# CCM_0021.net
KiCad netlist of a schematic drawn in EAGLE
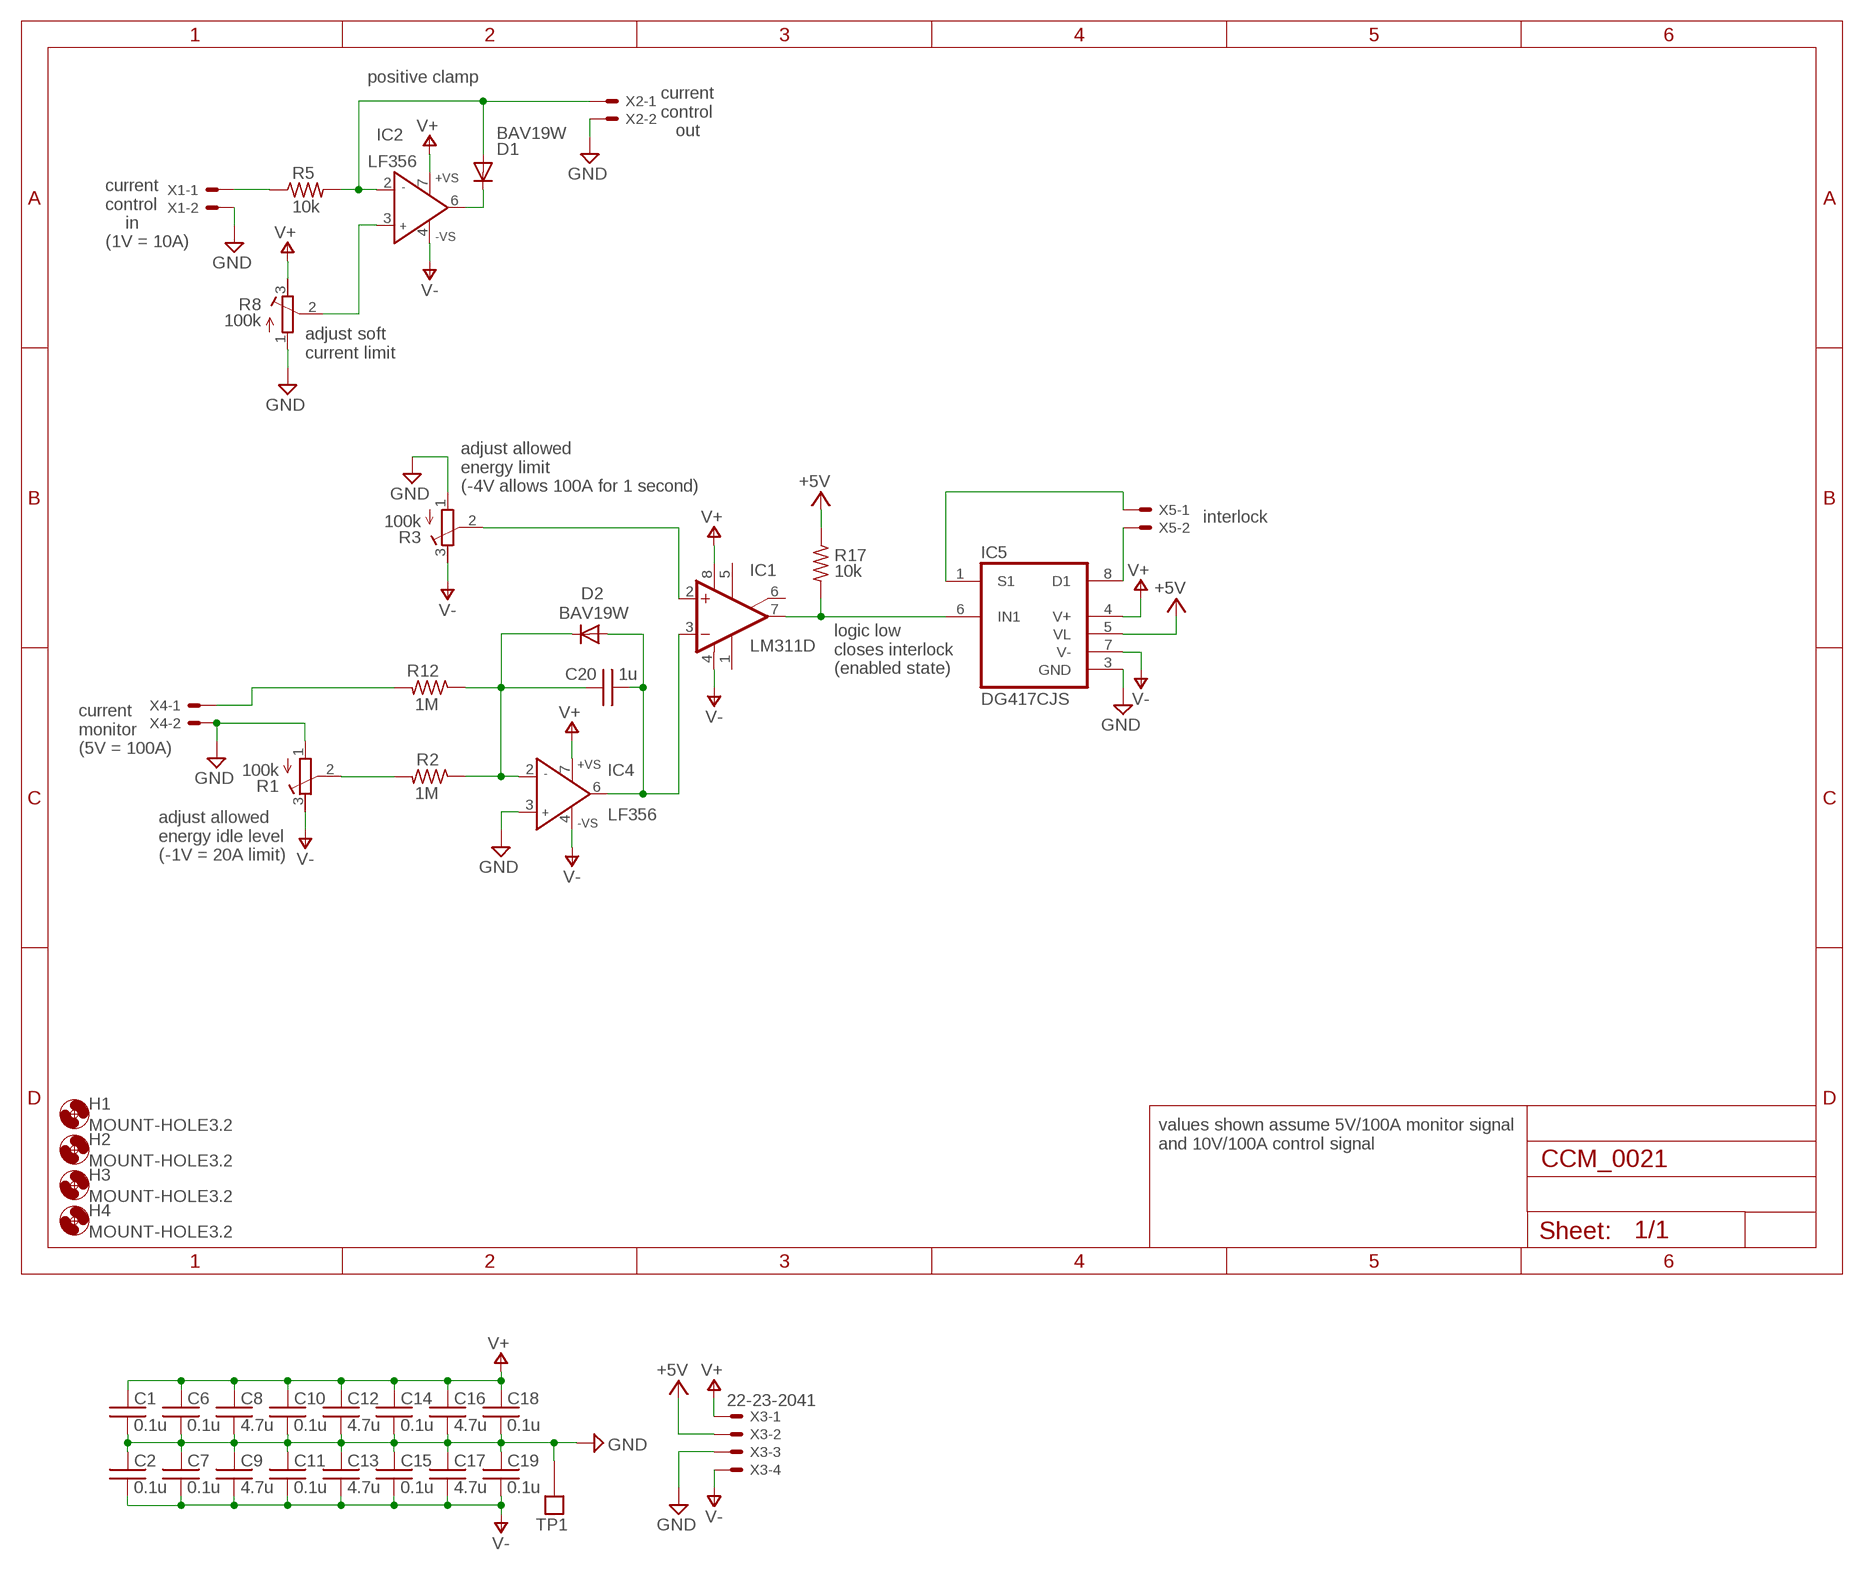
[diagram p0: schematic, sheet 1]

(export (version "E")
  (design (tool "Eeschema 10.0.6"))
  (components
    (comp (ref "C1")
      (value "0.1u")
      (footprint "eagle-import:0603")
      (libsource (lib "eagle-import") (part "C0603"))
    )
    (comp (ref "C2")
      (value "0.1u")
      (footprint "eagle-import:0603")
      (libsource (lib "eagle-import") (part "C0603"))
    )
    (comp (ref "C6")
      (value "0.1u")
      (footprint "eagle-import:0603")
      (libsource (lib "eagle-import") (part "C0603"))
    )
    (comp (ref "C7")
      (value "0.1u")
      (footprint "eagle-import:0603")
      (libsource (lib "eagle-import") (part "C0603"))
    )
    (comp (ref "C8")
      (value "4.7u")
      (footprint "eagle-import:0603")
      (libsource (lib "eagle-import") (part "C0603"))
    )
    (comp (ref "C9")
      (value "4.7u")
      (footprint "eagle-import:0603")
      (libsource (lib "eagle-import") (part "C0603"))
    )
    (comp (ref "C10")
      (value "0.1u")
      (footprint "eagle-import:0603")
      (libsource (lib "eagle-import") (part "C0603"))
    )
    (comp (ref "C11")
      (value "0.1u")
      (footprint "eagle-import:0603")
      (libsource (lib "eagle-import") (part "C0603"))
    )
    (comp (ref "C12")
      (value "4.7u")
      (footprint "eagle-import:0603")
      (libsource (lib "eagle-import") (part "C0603"))
    )
    (comp (ref "C13")
      (value "4.7u")
      (footprint "eagle-import:0603")
      (libsource (lib "eagle-import") (part "C0603"))
    )
    (comp (ref "C14")
      (value "0.1u")
      (footprint "eagle-import:0603")
      (libsource (lib "eagle-import") (part "C0603"))
    )
    (comp (ref "C15")
      (value "0.1u")
      (footprint "eagle-import:0603")
      (libsource (lib "eagle-import") (part "C0603"))
    )
    (comp (ref "C16")
      (value "4.7u")
      (footprint "eagle-import:0603")
      (libsource (lib "eagle-import") (part "C0603"))
    )
    (comp (ref "C17")
      (value "4.7u")
      (footprint "eagle-import:0603")
      (libsource (lib "eagle-import") (part "C0603"))
    )
    (comp (ref "C18")
      (value "0.1u")
      (footprint "eagle-import:0603")
      (libsource (lib "eagle-import") (part "C0603"))
    )
    (comp (ref "C19")
      (value "0.1u")
      (footprint "eagle-import:0603")
      (libsource (lib "eagle-import") (part "C0603"))
    )
    (comp (ref "C20")
      (value "1u")
      (footprint "eagle-import:0603")
      (libsource (lib "eagle-import") (part "C0603"))
    )
    (comp (ref "D1")
      (value "BAV19W")
      (footprint "eagle-import:SOD123")
      (libsource (lib "eagle-import") (part "DIODE-SOD123"))
    )
    (comp (ref "D2")
      (value "BAV19W")
      (footprint "eagle-import:SOD123")
      (libsource (lib "eagle-import") (part "DIODE-SOD123"))
    )
    (comp (ref "H1")
      (value "MOUNT-HOLE3.2")
      (footprint "eagle-import:3,2")
      (libsource (lib "eagle-import") (part "MOUNT-HOLE3.2"))
    )
    (comp (ref "H2")
      (value "MOUNT-HOLE3.2")
      (footprint "eagle-import:3,2")
      (libsource (lib "eagle-import") (part "MOUNT-HOLE3.2"))
    )
    (comp (ref "H3")
      (value "MOUNT-HOLE3.2")
      (footprint "eagle-import:3,2")
      (libsource (lib "eagle-import") (part "MOUNT-HOLE3.2"))
    )
    (comp (ref "H4")
      (value "MOUNT-HOLE3.2")
      (footprint "eagle-import:3,2")
      (libsource (lib "eagle-import") (part "MOUNT-HOLE3.2"))
    )
    (comp (ref "IC1")
      (value "LM311D")
      (footprint "eagle-import:SO08")
      (libsource (lib "eagle-import") (part "LM311D"))
    )
    (comp (ref "IC2")
      (value "LF356")
      (footprint "eagle-import:SO8")
      (fields (field (name "MF") "ALTERA CORPORATION") (field (name "MPN") "AD825ARZ"))
      (libsource (lib "eagle-import") (part "AD825_BR"))
    )
    (comp (ref "IC4")
      (value "LF356")
      (footprint "eagle-import:SO8")
      (fields (field (name "MF") "ALTERA CORPORATION") (field (name "MPN") "AD825ARZ"))
      (libsource (lib "eagle-import") (part "AD825_BR"))
    )
    (comp (ref "IC5")
      (value "DG417CJS")
      (footprint "eagle-import:SO8")
      (libsource (lib "eagle-import") (part "DG417CJS"))
    )
    (comp (ref "R1")
      (value "100k")
      (footprint "eagle-import:RTRIM3296W")
      (libsource (lib "eagle-import") (part "R-TRIMM3296W"))
    )
    (comp (ref "R2")
      (value "1M")
      (footprint "eagle-import:0603")
      (libsource (lib "eagle-import") (part "R0603"))
    )
    (comp (ref "R3")
      (value "100k")
      (footprint "eagle-import:RTRIM3296W")
      (libsource (lib "eagle-import") (part "R-TRIMM3296W"))
    )
    (comp (ref "R5")
      (value "10k")
      (footprint "eagle-import:0603")
      (libsource (lib "eagle-import") (part "R0603"))
    )
    (comp (ref "R8")
      (value "100k")
      (footprint "eagle-import:RTRIM3296W")
      (libsource (lib "eagle-import") (part "R-TRIMM3296W"))
    )
    (comp (ref "R12")
      (value "1M")
      (footprint "eagle-import:0603")
      (libsource (lib "eagle-import") (part "R0603"))
    )
    (comp (ref "R17")
      (value "10k")
      (footprint "eagle-import:0603")
      (libsource (lib "eagle-import") (part "R0603"))
    )
    (comp (ref "TP1")
      (value "TESTPOINT")
      (footprint "eagle-import:TESTPOINT")
      (libsource (lib "eagle-import") (part "TESTPOINT"))
    )
    (comp (ref "X1")
      (value "22-23-2021")
      (footprint "eagle-import:22-23-2021")
      (fields (field (name "MF") "MOLEX") (field (name "SPICEPREFIX") "X"))
      (libsource (lib "eagle-import") (part "22-23-2021"))
    )
    (comp (ref "X2")
      (value "22-23-2021")
      (footprint "eagle-import:22-23-2021")
      (fields (field (name "MF") "MOLEX"))
      (libsource (lib "eagle-import") (part "22-23-2021"))
    )
    (comp (ref "X3")
      (value "22-23-2041")
      (footprint "eagle-import:22-23-2041")
      (fields (field (name "MF") "MOLEX"))
      (libsource (lib "eagle-import") (part "22-23-2041"))
    )
    (comp (ref "X4")
      (value "22-23-2021")
      (footprint "eagle-import:22-23-2021")
      (fields (field (name "MF") "MOLEX") (field (name "SPICEPREFIX") "X"))
      (libsource (lib "eagle-import") (part "22-23-2021"))
    )
    (comp (ref "X5")
      (value "22-23-2021")
      (footprint "eagle-import:22-23-2021")
      (fields (field (name "MF") "MOLEX"))
      (libsource (lib "eagle-import") (part "22-23-2021"))
    )
  )
  (nets
    (net (code "1") (name "+5V") (class "Default")
      (node (ref "IC5") (pin "5") (pinfunction "VL_5") (pintype "power_in"))
      (node (ref "R17") (pin "1") (pinfunction "1_1") (pintype "passive"))
      (node (ref "X3") (pin "2") (pinfunction "S_2") (pintype "passive"))
    )
    (net (code "2") (name "GND") (class "Default")
      (node (ref "C1") (pin "2") (pinfunction "2_2") (pintype "passive"))
      (node (ref "C10") (pin "2") (pinfunction "2_2") (pintype "passive"))
      (node (ref "C11") (pin "1") (pinfunction "1_1") (pintype "passive"))
      (node (ref "C12") (pin "2") (pinfunction "2_2") (pintype "passive"))
      (node (ref "C13") (pin "1") (pinfunction "1_1") (pintype "passive"))
      (node (ref "C14") (pin "2") (pinfunction "2_2") (pintype "passive"))
      (node (ref "C15") (pin "1") (pinfunction "1_1") (pintype "passive"))
      (node (ref "C16") (pin "2") (pinfunction "2_2") (pintype "passive"))
      (node (ref "C17") (pin "1") (pinfunction "1_1") (pintype "passive"))
      (node (ref "C18") (pin "2") (pinfunction "2_2") (pintype "passive"))
      (node (ref "C19") (pin "1") (pinfunction "1_1") (pintype "passive"))
      (node (ref "C2") (pin "1") (pinfunction "1_1") (pintype "passive"))
      (node (ref "C6") (pin "2") (pinfunction "2_2") (pintype "passive"))
      (node (ref "C7") (pin "1") (pinfunction "1_1") (pintype "passive"))
      (node (ref "C8") (pin "2") (pinfunction "2_2") (pintype "passive"))
      (node (ref "C9") (pin "1") (pinfunction "1_1") (pintype "passive"))
      (node (ref "IC4") (pin "3") (pinfunction "IN+_3") (pintype "input"))
      (node (ref "IC5") (pin "3") (pinfunction "GND_3") (pintype "power_in"))
      (node (ref "R1") (pin "1") (pinfunction "A_1") (pintype "passive"))
      (node (ref "R3") (pin "1") (pinfunction "A_1") (pintype "passive"))
      (node (ref "R8") (pin "1") (pinfunction "A_1") (pintype "passive"))
      (node (ref "TP1") (pin "P$1") (pinfunction "P$1_P$1") (pintype "bidirectional"))
      (node (ref "X1") (pin "2") (pinfunction "S_2") (pintype "passive"))
      (node (ref "X2") (pin "2") (pinfunction "S_2") (pintype "passive"))
      (node (ref "X3") (pin "3") (pinfunction "S_3") (pintype "passive"))
      (node (ref "X4") (pin "2") (pinfunction "S_2") (pintype "passive"))
    )
    (net (code "3") (name "Net-(IC1-+IN)") (class "Default")
      (node (ref "IC1") (pin "2") (pinfunction "+IN_2") (pintype "input"))
      (node (ref "R3") (pin "2") (pinfunction "S_2") (pintype "passive"))
    )
    (net (code "4") (name "Net-(IC1--IN)") (class "Default")
      (node (ref "C20") (pin "1") (pinfunction "1_1") (pintype "passive"))
      (node (ref "D2") (pin "A") (pinfunction "A_A") (pintype "passive"))
      (node (ref "IC1") (pin "3") (pinfunction "-IN_3") (pintype "input"))
      (node (ref "IC4") (pin "6") (pinfunction "OUT_6") (pintype "output"))
    )
    (net (code "5") (name "Net-(IC1-OUT)") (class "Default")
      (node (ref "IC1") (pin "7") (pinfunction "OUT_7") (pintype "output"))
      (node (ref "IC5") (pin "6") (pinfunction "IN1_6") (pintype "input"))
      (node (ref "R17") (pin "2") (pinfunction "2_2") (pintype "passive"))
    )
    (net (code "6") (name "Net-(IC2-IN+)") (class "Default")
      (node (ref "IC2") (pin "3") (pinfunction "IN+_3") (pintype "input"))
      (node (ref "R8") (pin "2") (pinfunction "S_2") (pintype "passive"))
    )
    (net (code "7") (name "Net-(IC2-IN-)") (class "Default")
      (node (ref "D1") (pin "A") (pinfunction "A_A") (pintype "passive"))
      (node (ref "IC2") (pin "2") (pinfunction "IN-_2") (pintype "input"))
      (node (ref "R5") (pin "2") (pinfunction "2_2") (pintype "passive"))
      (node (ref "X2") (pin "1") (pinfunction "S_1") (pintype "passive"))
    )
    (net (code "8") (name "Net-(IC2-OUT)") (class "Default")
      (node (ref "D1") (pin "C") (pinfunction "C_C") (pintype "passive"))
      (node (ref "IC2") (pin "6") (pinfunction "OUT_6") (pintype "output"))
    )
    (net (code "9") (name "Net-(IC4-IN-)") (class "Default")
      (node (ref "C20") (pin "2") (pinfunction "2_2") (pintype "passive"))
      (node (ref "D2") (pin "C") (pinfunction "C_C") (pintype "passive"))
      (node (ref "IC4") (pin "2") (pinfunction "IN-_2") (pintype "input"))
      (node (ref "R12") (pin "1") (pinfunction "1_1") (pintype "passive"))
      (node (ref "R2") (pin "1") (pinfunction "1_1") (pintype "passive"))
    )
    (net (code "10") (name "Net-(IC5-D1)") (class "Default")
      (node (ref "IC5") (pin "8") (pinfunction "D1_8") (pintype "passive"))
      (node (ref "X5") (pin "2") (pinfunction "S_2") (pintype "passive"))
    )
    (net (code "11") (name "Net-(IC5-S1)") (class "Default")
      (node (ref "IC5") (pin "1") (pinfunction "S1_1") (pintype "passive"))
      (node (ref "X5") (pin "1") (pinfunction "S_1") (pintype "passive"))
    )
    (net (code "12") (name "Net-(R1-S)") (class "Default")
      (node (ref "R1") (pin "2") (pinfunction "S_2") (pintype "passive"))
      (node (ref "R2") (pin "2") (pinfunction "2_2") (pintype "passive"))
    )
    (net (code "13") (name "Net-(X1A-S)") (class "Default")
      (node (ref "R5") (pin "1") (pinfunction "1_1") (pintype "passive"))
      (node (ref "X1") (pin "1") (pinfunction "S_1") (pintype "passive"))
    )
    (net (code "14") (name "Net-(X4A-S)") (class "Default")
      (node (ref "R12") (pin "2") (pinfunction "2_2") (pintype "passive"))
      (node (ref "X4") (pin "1") (pinfunction "S_1") (pintype "passive"))
    )
    (net (code "15") (name "V+") (class "Default")
      (node (ref "C1") (pin "1") (pinfunction "1_1") (pintype "passive"))
      (node (ref "C10") (pin "1") (pinfunction "1_1") (pintype "passive"))
      (node (ref "C12") (pin "1") (pinfunction "1_1") (pintype "passive"))
      (node (ref "C14") (pin "1") (pinfunction "1_1") (pintype "passive"))
      (node (ref "C16") (pin "1") (pinfunction "1_1") (pintype "passive"))
      (node (ref "C18") (pin "1") (pinfunction "1_1") (pintype "passive"))
      (node (ref "C6") (pin "1") (pinfunction "1_1") (pintype "passive"))
      (node (ref "C8") (pin "1") (pinfunction "1_1") (pintype "passive"))
      (node (ref "IC1") (pin "8") (pinfunction "V+_8") (pintype "power_in"))
      (node (ref "IC2") (pin "7") (pinfunction "+VS_7") (pintype "input"))
      (node (ref "IC4") (pin "7") (pinfunction "+VS_7") (pintype "input"))
      (node (ref "IC5") (pin "4") (pinfunction "V+_4") (pintype "power_in"))
      (node (ref "R8") (pin "3") (pinfunction "E_3") (pintype "passive"))
      (node (ref "X3") (pin "1") (pinfunction "S_1") (pintype "passive"))
    )
    (net (code "16") (name "V-") (class "Default")
      (node (ref "C11") (pin "2") (pinfunction "2_2") (pintype "passive"))
      (node (ref "C13") (pin "2") (pinfunction "2_2") (pintype "passive"))
      (node (ref "C15") (pin "2") (pinfunction "2_2") (pintype "passive"))
      (node (ref "C17") (pin "2") (pinfunction "2_2") (pintype "passive"))
      (node (ref "C19") (pin "2") (pinfunction "2_2") (pintype "passive"))
      (node (ref "C2") (pin "2") (pinfunction "2_2") (pintype "passive"))
      (node (ref "C7") (pin "2") (pinfunction "2_2") (pintype "passive"))
      (node (ref "C9") (pin "2") (pinfunction "2_2") (pintype "passive"))
      (node (ref "IC1") (pin "4") (pinfunction "V-_4") (pintype "power_in"))
      (node (ref "IC2") (pin "4") (pinfunction "-VS_4") (pintype "input"))
      (node (ref "IC4") (pin "4") (pinfunction "-VS_4") (pintype "input"))
      (node (ref "IC5") (pin "7") (pinfunction "V-_7") (pintype "power_in"))
      (node (ref "R1") (pin "3") (pinfunction "E_3") (pintype "passive"))
      (node (ref "R3") (pin "3") (pinfunction "E_3") (pintype "passive"))
      (node (ref "X3") (pin "4") (pinfunction "S_4") (pintype "passive"))
    )
    (net (code "17") (name "unconnected-(IC1-GND-Pad1)") (class "Default")
      (node (ref "IC1") (pin "1") (pinfunction "GND_1") (pintype "passive"))
    )
    (net (code "18") (name "unconnected-(IC1-ON-Pad5)") (class "Default")
      (node (ref "IC1") (pin "5") (pinfunction "ON_5") (pintype "passive"))
    )
    (net (code "19") (name "unconnected-(IC1-ON{slash}STR-Pad6)") (class "Default")
      (node (ref "IC1") (pin "6") (pinfunction "ON/STR_6") (pintype "passive"))
    )
  )
)
